# untitled.net
KiCad netlist of a schematic drawn in EAGLE
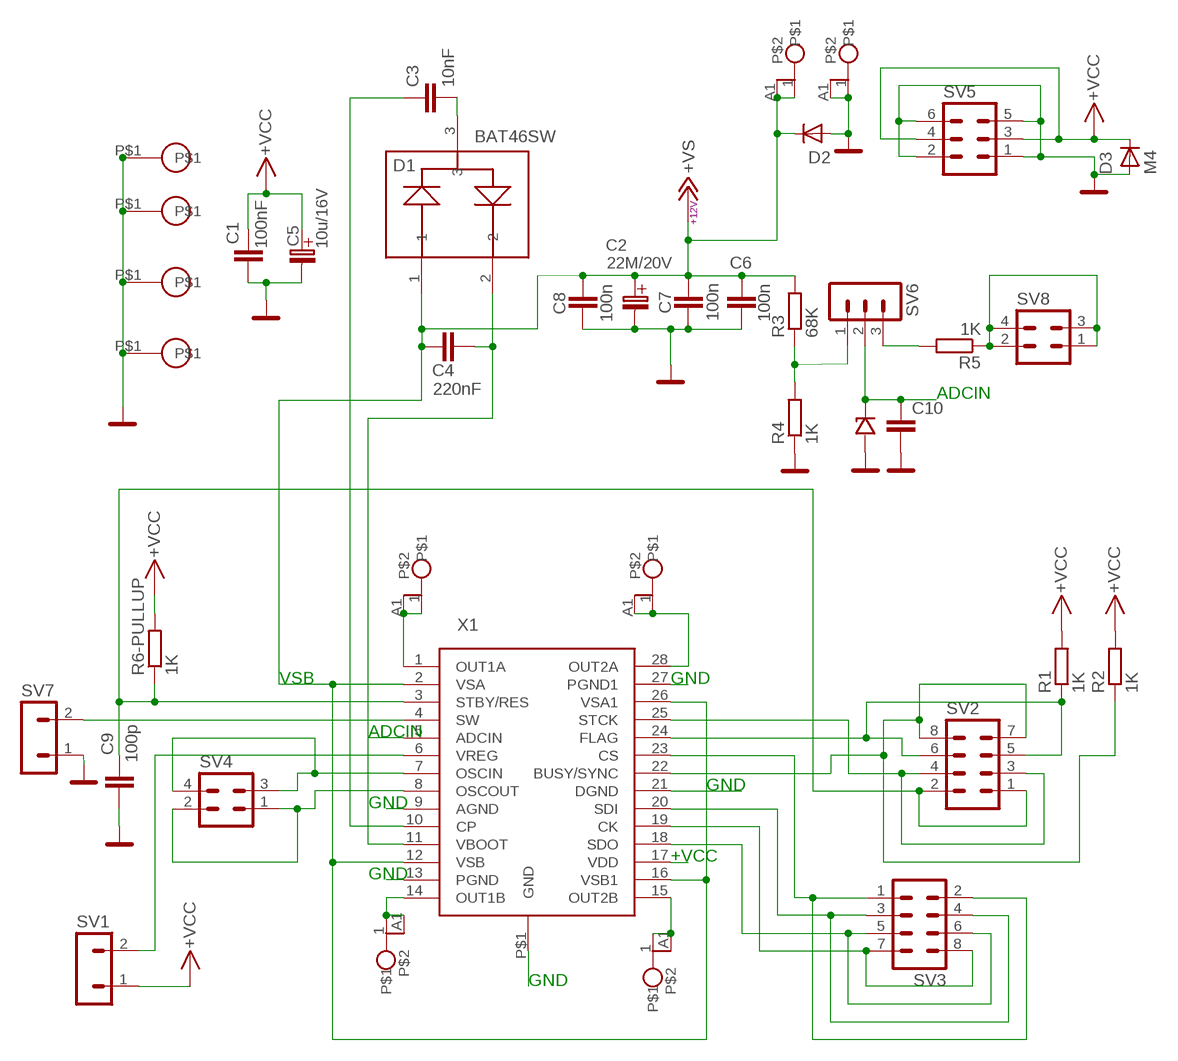
[diagram p0: schematic, sheet 1]

(export (version "E")
  (design (tool "Eeschema 10.0.6"))
  (components
    (comp (ref "C1")
      (value "100nF")
      (footprint "eagle-import:C0805")
      (libsource (lib "eagle-import") (part "C-EUC0805"))
    )
    (comp (ref "C2")
      (value "22M/20V")
      (footprint "eagle-import:D")
      (libsource (lib "eagle-import") (part "22M/20V"))
    )
    (comp (ref "C3")
      (value "10nF")
      (footprint "eagle-import:C0805")
      (libsource (lib "eagle-import") (part "C-EUC0805"))
    )
    (comp (ref "C4")
      (value "220nF")
      (footprint "eagle-import:C0805")
      (libsource (lib "eagle-import") (part "C-EUC0805"))
    )
    (comp (ref "C5")
      (value "10u/16V")
      (footprint "eagle-import:B")
      (libsource (lib "eagle-import") (part "1M/35V"))
    )
    (comp (ref "C6")
      (value "100n")
      (footprint "eagle-import:C0805")
      (libsource (lib "eagle-import") (part "C-EUC0805"))
    )
    (comp (ref "C7")
      (value "100n")
      (footprint "eagle-import:C0805")
      (libsource (lib "eagle-import") (part "C-EUC0805"))
    )
    (comp (ref "C8")
      (value "100n")
      (footprint "eagle-import:C0805")
      (libsource (lib "eagle-import") (part "C-EUC0805"))
    )
    (comp (ref "C9")
      (value "100p")
      (footprint "eagle-import:C0805")
      (libsource (lib "eagle-import") (part "C-EUC0805"))
    )
    (comp (ref "C10")
      (value "C-EUC0805")
      (footprint "eagle-import:C0805")
      (libsource (lib "eagle-import") (part "C-EUC0805"))
    )
    (comp (ref "CON1")
      (value "WAGO256")
      (footprint "eagle-import:WAGO256")
      (libsource (lib "eagle-import") (part "WAGO256"))
    )
    (comp (ref "CON2")
      (value "WAGO256")
      (footprint "eagle-import:WAGO256")
      (libsource (lib "eagle-import") (part "WAGO256"))
    )
    (comp (ref "CON3")
      (value "WAGO256")
      (footprint "eagle-import:WAGO256")
      (libsource (lib "eagle-import") (part "WAGO256"))
    )
    (comp (ref "CON4")
      (value "WAGO256")
      (footprint "eagle-import:WAGO256")
      (libsource (lib "eagle-import") (part "WAGO256"))
    )
    (comp (ref "CON5")
      (value "WAGO256")
      (footprint "eagle-import:WAGO256")
      (libsource (lib "eagle-import") (part "WAGO256"))
    )
    (comp (ref "CON6")
      (value "WAGO256")
      (footprint "eagle-import:WAGO256")
      (libsource (lib "eagle-import") (part "WAGO256"))
    )
    (comp (ref "D1")
      (value "BAT46SW")
      (footprint "eagle-import:SOT23")
      (libsource (lib "eagle-import") (part "BAR43S"))
    )
    (comp (ref "D2")
      (value "D-OB.")
      (footprint "eagle-import:SMB")
      (libsource (lib "eagle-import") (part "D-OB."))
    )
    (comp (ref "D3")
      (value "M4")
      (footprint "eagle-import:SMA")
      (libsource (lib "eagle-import") (part "D-OB.SMA"))
    )
    (comp (ref "D4")
      (value "D-ZENEROVA")
      (footprint "eagle-import:MINIMELF")
      (libsource (lib "eagle-import") (part "D-ZENEROVA"))
    )
    (comp (ref "R1")
      (value "1K")
      (footprint "eagle-import:R0805")
      (libsource (lib "eagle-import") (part "R-EU_R0805"))
    )
    (comp (ref "R2")
      (value "1K")
      (footprint "eagle-import:R0805")
      (libsource (lib "eagle-import") (part "R-EU_R0805"))
    )
    (comp (ref "R3")
      (value "68K")
      (footprint "eagle-import:R0805")
      (libsource (lib "eagle-import") (part "R-EU_R0805"))
    )
    (comp (ref "R4")
      (value "1K")
      (footprint "eagle-import:R0805")
      (libsource (lib "eagle-import") (part "R-EU_R0805"))
    )
    (comp (ref "R5")
      (value "1K")
      (footprint "eagle-import:R0805")
      (libsource (lib "eagle-import") (part "R-EU_R0805"))
    )
    (comp (ref "R6-PULLUP")
      (value "1K")
      (footprint "eagle-import:R0805")
      (libsource (lib "eagle-import") (part "R-EU_R0805"))
    )
    (comp (ref "SV1")
      (value "MA02-1")
      (footprint "eagle-import:MA02-1")
      (libsource (lib "eagle-import") (part "MA02-1"))
    )
    (comp (ref "SV2")
      (value "MA04-2")
      (footprint "eagle-import:MA04-2")
      (libsource (lib "eagle-import") (part "MA04-2"))
    )
    (comp (ref "SV3")
      (value "MA04-2")
      (footprint "eagle-import:MA04-2")
      (libsource (lib "eagle-import") (part "MA04-2"))
    )
    (comp (ref "SV4")
      (value "MA02-2")
      (footprint "eagle-import:MA02-2")
      (libsource (lib "eagle-import") (part "MA02-2"))
    )
    (comp (ref "SV5")
      (value "MA03-2")
      (footprint "eagle-import:MA03-2")
      (libsource (lib "eagle-import") (part "MA03-2"))
    )
    (comp (ref "SV6")
      (value "MA03-1")
      (footprint "eagle-import:MA03-1")
      (libsource (lib "eagle-import") (part "MA03-1"))
    )
    (comp (ref "SV7")
      (value "MA02-1")
      (footprint "eagle-import:MA02-1")
      (libsource (lib "eagle-import") (part "MA02-1"))
    )
    (comp (ref "SV8")
      (value "MA02-2")
      (footprint "eagle-import:MA02-2")
      (libsource (lib "eagle-import") (part "MA02-2"))
    )
    (comp (ref "X1")
      (value "L6470")
      (footprint "eagle-import:HTSSOP28")
      (libsource (lib "eagle-import") (part "L6470"))
    )
    (comp (ref "X3")
      (value "SROUB3M")
      (footprint "eagle-import:SROUB3M")
      (libsource (lib "eagle-import") (part "SROUB3M"))
    )
    (comp (ref "X4")
      (value "SROUB3M")
      (footprint "eagle-import:SROUB3M")
      (libsource (lib "eagle-import") (part "SROUB3M"))
    )
    (comp (ref "X5")
      (value "SROUB3M")
      (footprint "eagle-import:SROUB3M")
      (libsource (lib "eagle-import") (part "SROUB3M"))
    )
    (comp (ref "X6")
      (value "SROUB3M")
      (footprint "eagle-import:SROUB3M")
      (libsource (lib "eagle-import") (part "SROUB3M"))
    )
  )
  (nets
    (net (code "1") (name "+VCC") (class "Default")
      (node (ref "C1") (pin "1") (pinfunction "1_1") (pintype "passive"))
      (node (ref "C5") (pin "+") (pinfunction "C_EL+_+") (pintype "passive"))
      (node (ref "D3") (pin "K") (pinfunction "C_K") (pintype "passive"))
      (node (ref "R1") (pin "2") (pinfunction "2_2") (pintype "passive"))
      (node (ref "R2") (pin "2") (pinfunction "2_2") (pintype "passive"))
      (node (ref "R6-PULLUP") (pin "2") (pinfunction "2_2") (pintype "passive"))
      (node (ref "SV1") (pin "1") (pinfunction "1_1") (pintype "passive"))
      (node (ref "SV5") (pin "3") (pinfunction "3_3") (pintype "passive"))
      (node (ref "SV5") (pin "4") (pinfunction "4_4") (pintype "passive"))
      (node (ref "X1") (pin "17") (pinfunction "VDD_17") (pintype "bidirectional"))
    )
    (net (code "2") (name "+VS") (class "Default")
      (node (ref "C2") (pin "+") (pinfunction "C_EL+_+") (pintype "passive"))
      (node (ref "C4") (pin "1") (pinfunction "1_1") (pintype "passive"))
      (node (ref "C6") (pin "1") (pinfunction "1_1") (pintype "passive"))
      (node (ref "C7") (pin "1") (pinfunction "1_1") (pintype "passive"))
      (node (ref "C8") (pin "1") (pinfunction "1_1") (pintype "passive"))
      (node (ref "CON6") (pin "1") (pinfunction "P$1_1") (pintype "passive"))
      (node (ref "CON6") (pin "A1") (pinfunction "P$2_A1") (pintype "passive"))
      (node (ref "D1") (pin "1") (pinfunction "1_1") (pintype "bidirectional"))
      (node (ref "D2") (pin "K") (pinfunction "C_K") (pintype "passive"))
      (node (ref "R3") (pin "2") (pinfunction "2_2") (pintype "passive"))
      (node (ref "X1") (pin "12") (pinfunction "VSB_12") (pintype "bidirectional"))
      (node (ref "X1") (pin "16") (pinfunction "VSB1_16") (pintype "bidirectional"))
      (node (ref "X1") (pin "2") (pinfunction "VSA_2") (pintype "bidirectional"))
      (node (ref "X1") (pin "26") (pinfunction "VSA1_26") (pintype "bidirectional"))
    )
    (net (code "3") (name "/ADCIN") (class "Default")
      (node (ref "C10") (pin "1") (pinfunction "1_1") (pintype "passive"))
      (node (ref "D4") (pin "C") (pinfunction "K_C") (pintype "passive"))
      (node (ref "SV6") (pin "2") (pinfunction "2_2") (pintype "passive"))
      (node (ref "X1") (pin "5") (pinfunction "ADCIN_5") (pintype "bidirectional"))
    )
    (net (code "4") (name "GND") (class "Default")
      (node (ref "C1") (pin "2") (pinfunction "2_2") (pintype "passive"))
      (node (ref "C10") (pin "2") (pinfunction "2_2") (pintype "passive"))
      (node (ref "C2") (pin "-") (pinfunction "C_EL-_-") (pintype "passive"))
      (node (ref "C5") (pin "-") (pinfunction "C_EL-_-") (pintype "passive"))
      (node (ref "C6") (pin "2") (pinfunction "2_2") (pintype "passive"))
      (node (ref "C7") (pin "2") (pinfunction "2_2") (pintype "passive"))
      (node (ref "C8") (pin "2") (pinfunction "2_2") (pintype "passive"))
      (node (ref "C9") (pin "2") (pinfunction "2_2") (pintype "passive"))
      (node (ref "CON5") (pin "1") (pinfunction "P$1_1") (pintype "passive"))
      (node (ref "CON5") (pin "A1") (pinfunction "P$2_A1") (pintype "passive"))
      (node (ref "D2") (pin "A") (pinfunction "A_A") (pintype "passive"))
      (node (ref "D3") (pin "A") (pinfunction "A_A") (pintype "passive"))
      (node (ref "D4") (pin "A") (pinfunction "A_A") (pintype "passive"))
      (node (ref "R4") (pin "1") (pinfunction "1_1") (pintype "passive"))
      (node (ref "SV5") (pin "1") (pinfunction "1_1") (pintype "passive"))
      (node (ref "SV5") (pin "2") (pinfunction "2_2") (pintype "passive"))
      (node (ref "SV5") (pin "5") (pinfunction "5_5") (pintype "passive"))
      (node (ref "SV5") (pin "6") (pinfunction "6_6") (pintype "passive"))
      (node (ref "SV7") (pin "1") (pinfunction "1_1") (pintype "passive"))
      (node (ref "X1") (pin "13") (pinfunction "PGND_13") (pintype "bidirectional"))
      (node (ref "X1") (pin "21") (pinfunction "DGND_21") (pintype "bidirectional"))
      (node (ref "X1") (pin "27") (pinfunction "PGND1_27") (pintype "bidirectional"))
      (node (ref "X1") (pin "9") (pinfunction "AGND_9") (pintype "bidirectional"))
      (node (ref "X1") (pin "P$1") (pinfunction "GND_P$1") (pintype "bidirectional"))
      (node (ref "X3") (pin "P$1") (pinfunction "P$1_P$1") (pintype "output"))
      (node (ref "X4") (pin "P$1") (pinfunction "P$1_P$1") (pintype "output"))
      (node (ref "X5") (pin "P$1") (pinfunction "P$1_P$1") (pintype "output"))
      (node (ref "X6") (pin "P$1") (pinfunction "P$1_P$1") (pintype "output"))
    )
    (net (code "5") (name "Net-(C3-Pad2)") (class "Default")
      (node (ref "C3") (pin "2") (pinfunction "2_2") (pintype "passive"))
      (node (ref "D1") (pin "3") (pinfunction "3_3") (pintype "bidirectional"))
    )
    (net (code "6") (name "Net-(CON1-P$1)") (class "Default")
      (node (ref "CON1") (pin "1") (pinfunction "P$1_1") (pintype "passive"))
      (node (ref "CON1") (pin "A1") (pinfunction "P$2_A1") (pintype "passive"))
      (node (ref "X1") (pin "14") (pinfunction "OUT1B_14") (pintype "bidirectional"))
    )
    (net (code "7") (name "Net-(CON2-P$1)") (class "Default")
      (node (ref "CON2") (pin "1") (pinfunction "P$1_1") (pintype "passive"))
      (node (ref "CON2") (pin "A1") (pinfunction "P$2_A1") (pintype "passive"))
      (node (ref "X1") (pin "15") (pinfunction "OUT2B_15") (pintype "bidirectional"))
    )
    (net (code "8") (name "Net-(CON3-P$1)") (class "Default")
      (node (ref "CON3") (pin "1") (pinfunction "P$1_1") (pintype "passive"))
      (node (ref "CON3") (pin "A1") (pinfunction "P$2_A1") (pintype "passive"))
      (node (ref "X1") (pin "1") (pinfunction "OUT1A_1") (pintype "bidirectional"))
    )
    (net (code "9") (name "Net-(CON4-P$1)") (class "Default")
      (node (ref "CON4") (pin "1") (pinfunction "P$1_1") (pintype "passive"))
      (node (ref "CON4") (pin "A1") (pinfunction "P$2_A1") (pintype "passive"))
      (node (ref "X1") (pin "28") (pinfunction "OUT2A_28") (pintype "bidirectional"))
    )
    (net (code "10") (name "Net-(R3-Pad1)") (class "Default")
      (node (ref "R3") (pin "1") (pinfunction "1_1") (pintype "passive"))
      (node (ref "R4") (pin "2") (pinfunction "2_2") (pintype "passive"))
      (node (ref "SV6") (pin "1") (pinfunction "1_1") (pintype "passive"))
    )
    (net (code "11") (name "Net-(R5-Pad1)") (class "Default")
      (node (ref "R5") (pin "1") (pinfunction "1_1") (pintype "passive"))
      (node (ref "SV8") (pin "1") (pinfunction "1_1") (pintype "passive"))
      (node (ref "SV8") (pin "2") (pinfunction "2_2") (pintype "passive"))
      (node (ref "SV8") (pin "3") (pinfunction "3_3") (pintype "passive"))
      (node (ref "SV8") (pin "4") (pinfunction "4_4") (pintype "passive"))
    )
    (net (code "12") (name "Net-(R5-Pad2)") (class "Default")
      (node (ref "R5") (pin "2") (pinfunction "2_2") (pintype "passive"))
      (node (ref "SV6") (pin "3") (pinfunction "3_3") (pintype "passive"))
    )
    (net (code "13") (name "Net-(SV1-3)") (class "Default")
      (node (ref "SV1") (pin "2") (pinfunction "3_2") (pintype "passive"))
      (node (ref "X1") (pin "6") (pinfunction "VREG_6") (pintype "bidirectional"))
    )
    (net (code "14") (name "Net-(SV7-3)") (class "Default")
      (node (ref "SV7") (pin "2") (pinfunction "3_2") (pintype "passive"))
      (node (ref "X1") (pin "4") (pinfunction "SW_4") (pintype "bidirectional"))
    )
    (net (code "15") (name "Net-(X1-BUSY{slash}SYNC)") (class "Default")
      (node (ref "R2") (pin "1") (pinfunction "1_1") (pintype "passive"))
      (node (ref "SV2") (pin "7") (pinfunction "7_7") (pintype "passive"))
      (node (ref "SV2") (pin "8") (pinfunction "8_8") (pintype "passive"))
      (node (ref "X1") (pin "22") (pinfunction "BUSY/SYNC_22") (pintype "bidirectional"))
    )
    (net (code "16") (name "Net-(X1-CK)") (class "Default")
      (node (ref "SV3") (pin "7") (pinfunction "7_7") (pintype "passive"))
      (node (ref "SV3") (pin "8") (pinfunction "8_8") (pintype "passive"))
      (node (ref "X1") (pin "19") (pinfunction "CK_19") (pintype "bidirectional"))
    )
    (net (code "17") (name "Net-(X1-CP)") (class "Default")
      (node (ref "C3") (pin "1") (pinfunction "1_1") (pintype "passive"))
      (node (ref "X1") (pin "10") (pinfunction "CP_10") (pintype "bidirectional"))
    )
    (net (code "18") (name "Net-(X1-CS)") (class "Default")
      (node (ref "SV3") (pin "1") (pinfunction "1_1") (pintype "passive"))
      (node (ref "SV3") (pin "2") (pinfunction "2_2") (pintype "passive"))
      (node (ref "X1") (pin "23") (pinfunction "CS_23") (pintype "bidirectional"))
    )
    (net (code "19") (name "Net-(X1-FLAG)") (class "Default")
      (node (ref "R1") (pin "1") (pinfunction "1_1") (pintype "passive"))
      (node (ref "SV2") (pin "5") (pinfunction "5_5") (pintype "passive"))
      (node (ref "SV2") (pin "6") (pinfunction "6_6") (pintype "passive"))
      (node (ref "X1") (pin "24") (pinfunction "FLAG_24") (pintype "bidirectional"))
    )
    (net (code "20") (name "Net-(X1-OSCIN)") (class "Default")
      (node (ref "SV4") (pin "3") (pinfunction "3_3") (pintype "passive"))
      (node (ref "SV4") (pin "4") (pinfunction "4_4") (pintype "passive"))
      (node (ref "X1") (pin "7") (pinfunction "OSCIN_7") (pintype "bidirectional"))
    )
    (net (code "21") (name "Net-(X1-OSCOUT)") (class "Default")
      (node (ref "SV4") (pin "1") (pinfunction "1_1") (pintype "passive"))
      (node (ref "SV4") (pin "2") (pinfunction "2_2") (pintype "passive"))
      (node (ref "X1") (pin "8") (pinfunction "OSCOUT_8") (pintype "bidirectional"))
    )
    (net (code "22") (name "Net-(X1-SDI)") (class "Default")
      (node (ref "SV3") (pin "3") (pinfunction "3_3") (pintype "passive"))
      (node (ref "SV3") (pin "4") (pinfunction "4_4") (pintype "passive"))
      (node (ref "X1") (pin "20") (pinfunction "SDI_20") (pintype "bidirectional"))
    )
    (net (code "23") (name "Net-(X1-SDO)") (class "Default")
      (node (ref "SV3") (pin "5") (pinfunction "5_5") (pintype "passive"))
      (node (ref "SV3") (pin "6") (pinfunction "6_6") (pintype "passive"))
      (node (ref "X1") (pin "18") (pinfunction "SDO_18") (pintype "bidirectional"))
    )
    (net (code "24") (name "Net-(X1-STBY{slash}RES)") (class "Default")
      (node (ref "C9") (pin "1") (pinfunction "1_1") (pintype "passive"))
      (node (ref "R6-PULLUP") (pin "1") (pinfunction "1_1") (pintype "passive"))
      (node (ref "SV2") (pin "1") (pinfunction "1_1") (pintype "passive"))
      (node (ref "SV2") (pin "2") (pinfunction "2_2") (pintype "passive"))
      (node (ref "X1") (pin "3") (pinfunction "STBY/RES_3") (pintype "bidirectional"))
    )
    (net (code "25") (name "Net-(X1-STCK)") (class "Default")
      (node (ref "SV2") (pin "3") (pinfunction "3_3") (pintype "passive"))
      (node (ref "SV2") (pin "4") (pinfunction "4_4") (pintype "passive"))
      (node (ref "X1") (pin "25") (pinfunction "STCK_25") (pintype "bidirectional"))
    )
    (net (code "26") (name "Net-(X1-VBOOT)") (class "Default")
      (node (ref "C4") (pin "2") (pinfunction "2_2") (pintype "passive"))
      (node (ref "D1") (pin "2") (pinfunction "2_2") (pintype "bidirectional"))
      (node (ref "X1") (pin "11") (pinfunction "VBOOT_11") (pintype "bidirectional"))
    )
  )
)
